# HV_DAC_8ch_DAC_channel.net
KiCad netlist of a schematic drawn in Altium Designer
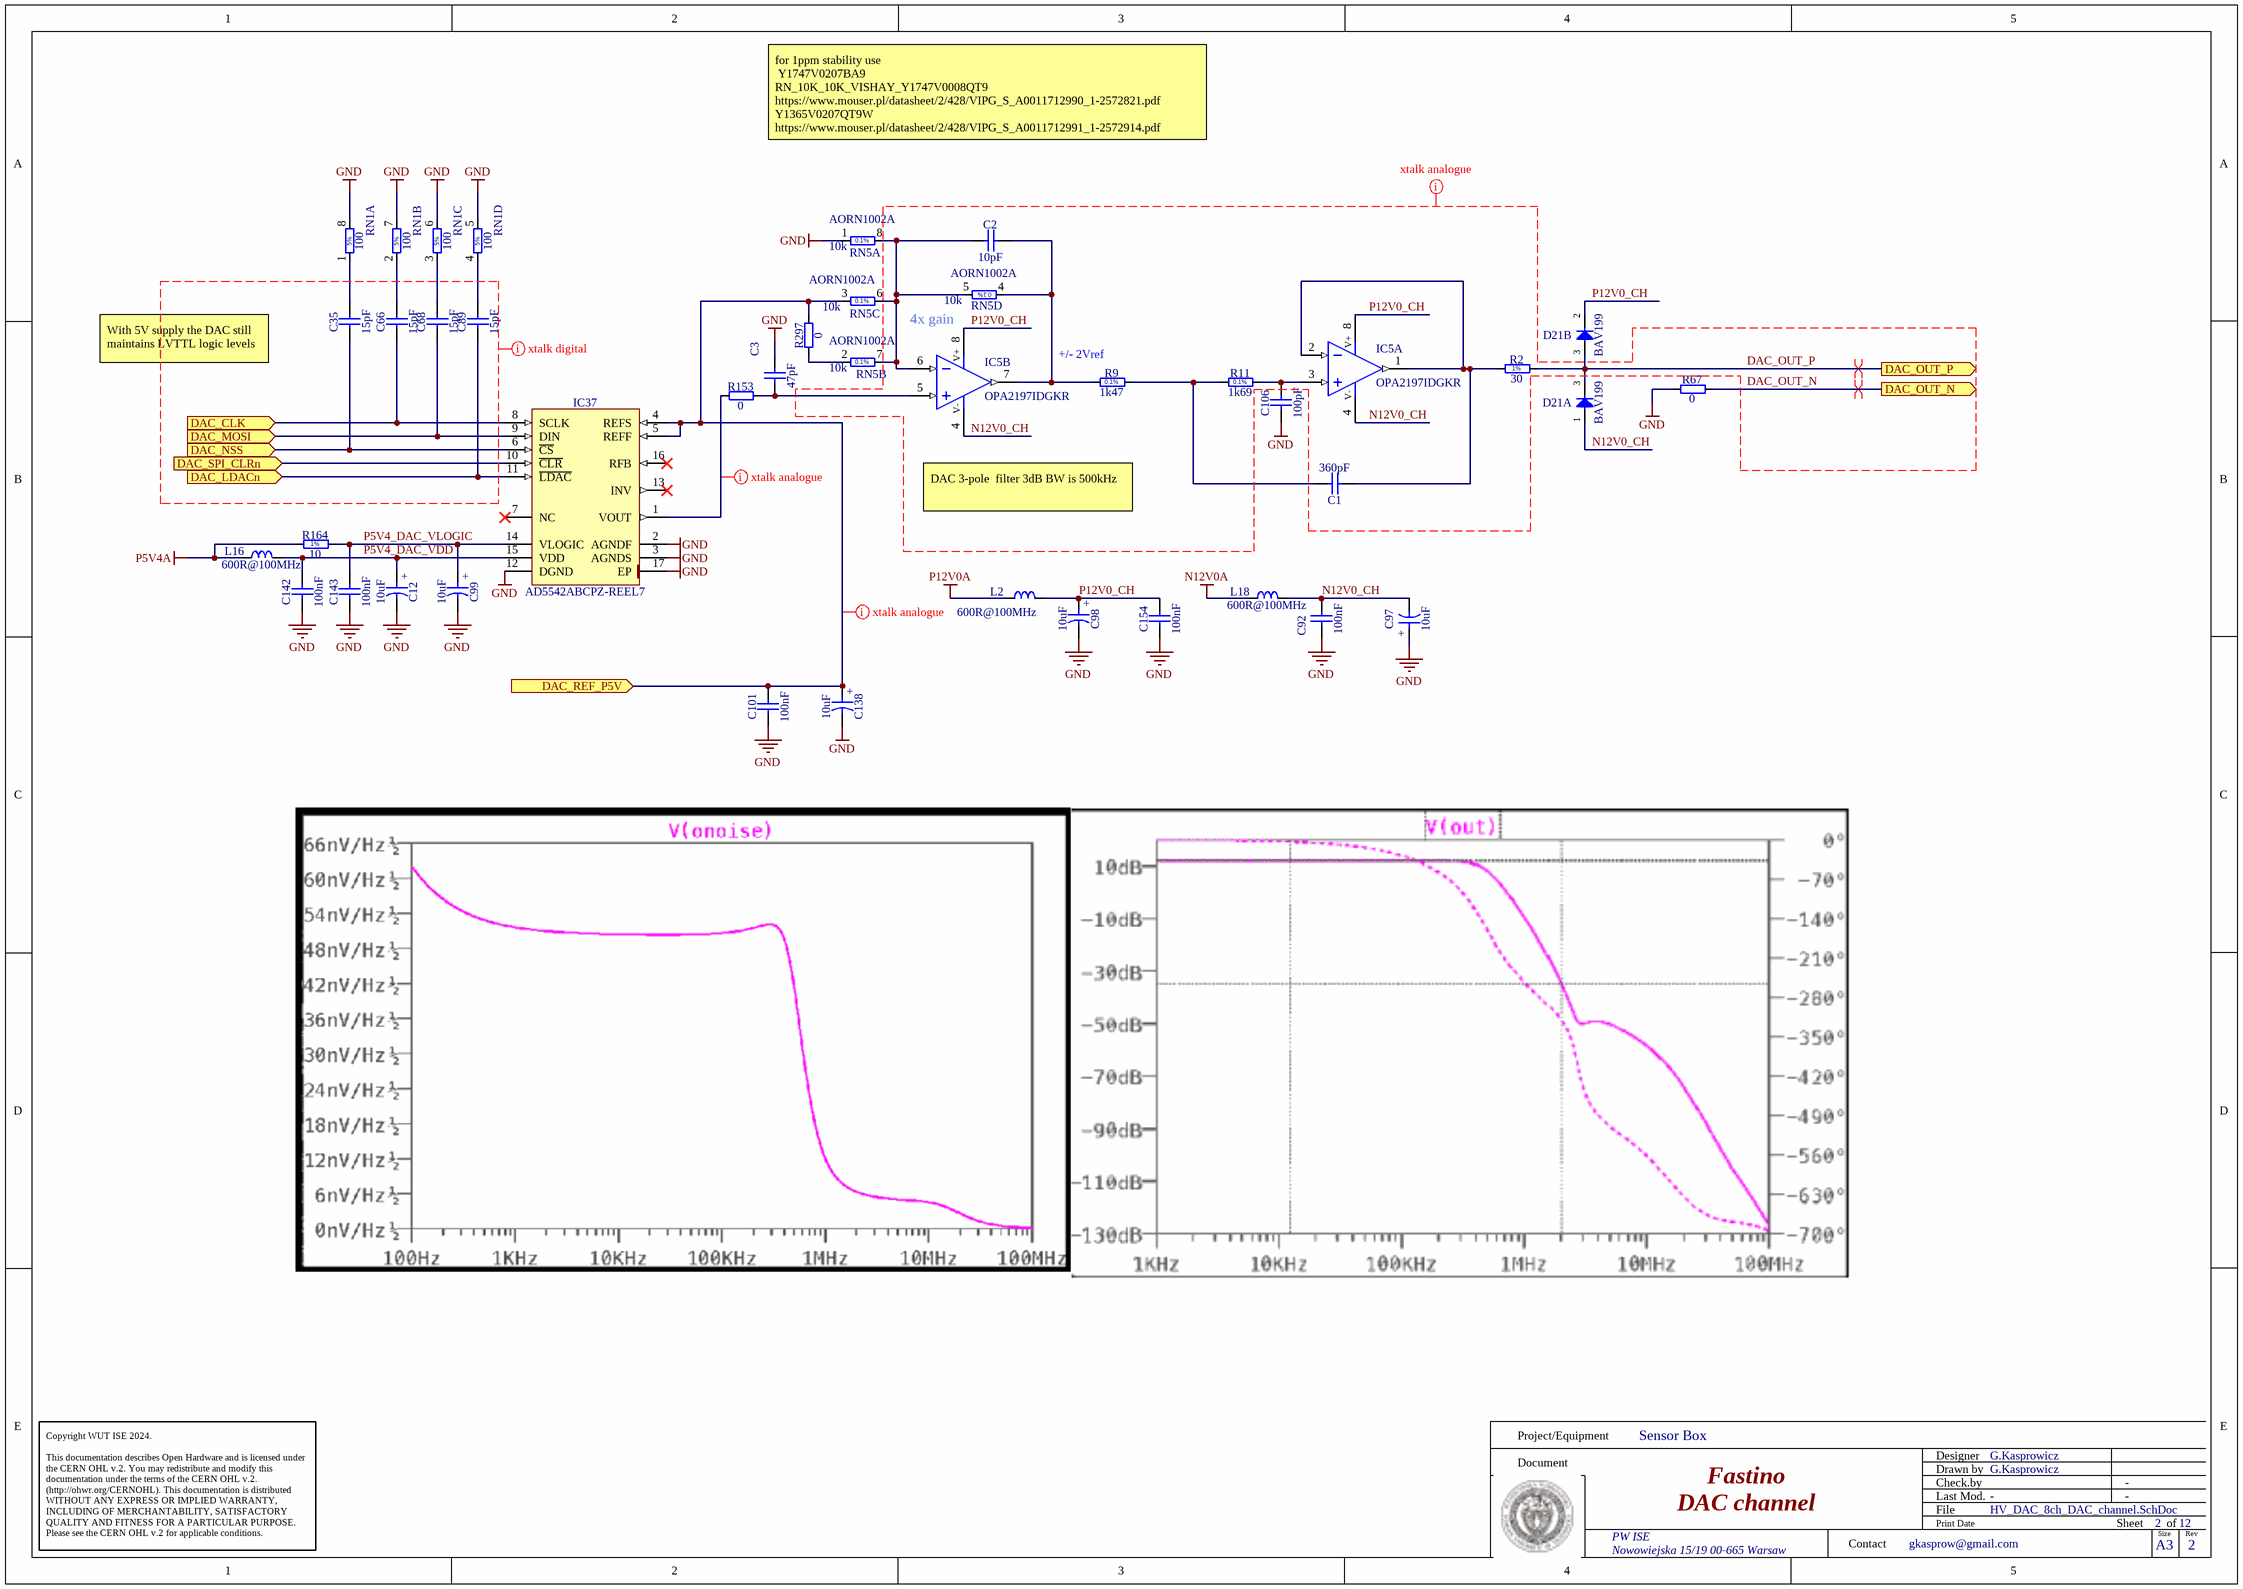
[diagram p0: HV_DAC_8ch_DAC_channel.SchDoc]

(export (version "E")
  (design (tool "Eeschema 10.0.6"))
  (components
    (comp (ref "C1")
      (value "360pF")
      (footprint "CAPC1608X90N")
      (description "SMD Multilayer Chip Ceramic Capacitor")
      (fields
        (field (name "PART NUMBER") "CC0603_360PF_25V_1%_C0G")
        (field (name "VOLTAGE") "25")
        (field (name "AUTHOR") "GK")
      )
      (libsource (lib "Passives_RC") (part "CC0603_360PF_25V_1%_C0G"))
    )
    (comp (ref "C2")
      (value "10pF")
      (footprint "CAPC1005X55N")
      (description "Non-polarised capacitor")
      (fields
        (field (name "PART NUMBER") "CC0402_10PF_50V_5%_C0G")
        (field (name "VOLTAGE") "50V")
        (field (name "AUTHOR") "CERN DEM JLC")
      )
      (libsource (lib "Capacitors") (part "Capacitor - non polarized"))
    )
    (comp (ref "C3")
      (value "47pF")
      (footprint "CAPC1005X55N")
      (description "Non-polarised capacitor")
      (fields
        (field (name "PART NUMBER") "CC0402_47PF_50V_1%_C0G_MURATA_GJM1555C1H470FB01D")
        (field (name "VOLTAGE") "50V")
        (field (name "AUTHOR") "CERN DEM BC")
      )
      (libsource (lib "Capacitors") (part "Capacitor - non polarized"))
    )
    (comp (ref "C12")
      (value "10uF")
      (footprint "CAPMP3216X180N")
      (description "Polarised capacitor")
      (fields
        (field (name "PART NUMBER") "CTE3216-18_10UF_16V_20%_AVX_TCJ")
        (field (name "VOLTAGE") "16V")
        (field (name "AUTHOR") "CERN DEM JLC")
      )
      (libsource (lib "Capacitors") (part "Capacitor - polarized"))
    )
    (comp (ref "C35")
      (value "15pF")
      (footprint "CAPC1608X87N")
      (description "Non-polarised capacitor")
      (fields
        (field (name "PART NUMBER") "CC0603_15PF_50V_5%_NP0")
        (field (name "VOLTAGE") "50V")
        (field (name "AUTHOR") "CERN DEM JLC")
      )
      (libsource (lib "Capacitors") (part "Capacitor - non polarized"))
    )
    (comp (ref "C66")
      (value "15pF")
      (footprint "CAPC1608X87N")
      (description "Non-polarised capacitor")
      (fields
        (field (name "PART NUMBER") "CC0603_15PF_50V_5%_NP0")
        (field (name "VOLTAGE") "50V")
        (field (name "AUTHOR") "CERN DEM JLC")
      )
      (libsource (lib "Capacitors") (part "Capacitor - non polarized"))
    )
    (comp (ref "C68")
      (value "15pF")
      (footprint "CAPC1608X87N")
      (description "Non-polarised capacitor")
      (fields
        (field (name "PART NUMBER") "CC0603_15PF_50V_5%_NP0")
        (field (name "VOLTAGE") "50V")
        (field (name "AUTHOR") "CERN DEM JLC")
      )
      (libsource (lib "Capacitors") (part "Capacitor - non polarized"))
    )
    (comp (ref "C89")
      (value "15pF")
      (footprint "CAPC1608X87N")
      (description "Non-polarised capacitor")
      (fields
        (field (name "PART NUMBER") "CC0603_15PF_50V_5%_NP0")
        (field (name "VOLTAGE") "50V")
        (field (name "AUTHOR") "CERN DEM JLC")
      )
      (libsource (lib "Capacitors") (part "Capacitor - non polarized"))
    )
    (comp (ref "C92")
      (value "100nF")
      (footprint "CAPC1005X55N")
      (description "Non-polarised capacitor")
      (fields
        (field (name "PART NUMBER") "CC0402_100NF_16V_10%_X7R")
        (field (name "VOLTAGE") "16V")
        (field (name "AUTHOR") "CERN DEM JLC")
      )
      (libsource (lib "Capacitors") (part "Capacitor - non polarized"))
    )
    (comp (ref "C97")
      (value "10uF")
      (footprint "CAPMP3216X180N")
      (description "Polarised capacitor")
      (fields
        (field (name "PART NUMBER") "CTE3216-18_10UF_16V_20%_AVX_TCJ")
        (field (name "VOLTAGE") "16V")
        (field (name "AUTHOR") "CERN DEM JLC")
      )
      (libsource (lib "Capacitors") (part "Capacitor - polarized"))
    )
    (comp (ref "C98")
      (value "10uF")
      (footprint "CAPMP3216X180N")
      (description "Polarised capacitor")
      (fields
        (field (name "PART NUMBER") "CTE3216-18_10UF_16V_20%_AVX_TCJ")
        (field (name "VOLTAGE") "16V")
        (field (name "AUTHOR") "CERN DEM JLC")
      )
      (libsource (lib "Capacitors") (part "Capacitor - polarized"))
    )
    (comp (ref "C99")
      (value "10uF")
      (footprint "CAPMP3216X180N")
      (description "Polarised capacitor")
      (fields
        (field (name "PART NUMBER") "CTE3216-18_10UF_16V_20%_AVX_TCJ")
        (field (name "VOLTAGE") "16V")
        (field (name "AUTHOR") "CERN DEM JLC")
      )
      (libsource (lib "Capacitors") (part "Capacitor - polarized"))
    )
    (comp (ref "C101")
      (value "100nF")
      (footprint "CAPC1005X55N")
      (description "Non-polarised capacitor")
      (fields
        (field (name "PART NUMBER") "CC0402_100NF_16V_10%_X7R")
        (field (name "VOLTAGE") "16V")
        (field (name "AUTHOR") "CERN DEM JLC")
      )
      (libsource (lib "Capacitors") (part "Capacitor - non polarized"))
    )
    (comp (ref "C106")
      (value "100pF")
      (footprint "CAPC1608X90N")
      (description "Non-polarised capacitor")
      (fields
        (field (name "PART NUMBER") "CC0603_100PF_50V_1%_NP0")
        (field (name "VOLTAGE") "50V")
        (field (name "AUTHOR") "CERN DEM JLC")
      )
      (libsource (lib "Capacitors") (part "Capacitor - non polarized"))
    )
    (comp (ref "C138")
      (value "10uF")
      (footprint "CAPMP3216X180N")
      (description "Polarised capacitor")
      (fields
        (field (name "PART NUMBER") "CTE3216-18_10UF_16V_20%_AVX_TCJ")
        (field (name "VOLTAGE") "16V")
        (field (name "AUTHOR") "CERN DEM JLC")
      )
      (libsource (lib "Capacitors") (part "Capacitor - polarized"))
    )
    (comp (ref "C142")
      (value "100nF")
      (footprint "CAPC1005X55N")
      (description "Non-polarised capacitor")
      (fields
        (field (name "PART NUMBER") "CC0402_100NF_16V_10%_X7R")
        (field (name "VOLTAGE") "16V")
        (field (name "AUTHOR") "CERN DEM JLC")
      )
      (libsource (lib "Capacitors") (part "Capacitor - non polarized"))
    )
    (comp (ref "C143")
      (value "100nF")
      (footprint "CAPC1005X55N")
      (description "Non-polarised capacitor")
      (fields
        (field (name "PART NUMBER") "CC0402_100NF_16V_10%_X7R")
        (field (name "VOLTAGE") "16V")
        (field (name "AUTHOR") "CERN DEM JLC")
      )
      (libsource (lib "Capacitors") (part "Capacitor - non polarized"))
    )
    (comp (ref "C154")
      (value "100nF")
      (footprint "CAPC1005X55N")
      (description "Non-polarised capacitor")
      (fields
        (field (name "PART NUMBER") "CC0402_100NF_16V_10%_X7R")
        (field (name "VOLTAGE") "16V")
        (field (name "AUTHOR") "CERN DEM JLC")
      )
      (libsource (lib "Capacitors") (part "Capacitor - non polarized"))
    )
    (comp (ref "D21")
      (value "BAV199")
      (footprint "SOT95P240X110-3N")
      (description "Serial Diode")
      (fields
        (field (name "VOLTAGE") "75V")
        (field (name "POWER") "250mW")
        (field (name "AUTHOR") "CERN DEM JMW")
      )
      (libsource (lib "ICs And Semiconductors") (part "Diode x2 A1C3_A3C2"))
    )
    (comp (ref "IC5")
      (value "OPA2197IDGKR")
      (footprint "SOP65P490X110-8N")
      (description "36-V, Precision, Rail-to-Rail Input Output, Low Offset Voltage Op Amp 8-VSSOP")
      (fields (field (name "MANUFACTURER") "TEXAS INSTRUMENTS") (field (name "AUTHOR") "GK"))
      (libsource (lib "ICs_Analog_Interfaces") (part "OA_OPA2197IDGKR"))
    )
    (comp (ref "IC37")
      (value "AD5542ABCPZ-REEL7")
      (footprint "QFN50P300X300X80-17N-S175")
      (description "2.7V to 5.5V, Serial-Input, Voltage-Output, 16-Bit DAC")
      (fields (field (name "MANUFACTURER") "ANALOG DEVICES") (field (name "AUTHOR") "CERN DEM JLC"))
      (libsource (lib "ICs And Semiconductors") (part "AD5542ABCPZ"))
    )
    (comp (ref "L2")
      (value "600R@100MHz")
      (footprint "INDC1005X55N")
      (description "Inductor")
      (fields
        (field (name "PART NUMBER") "IND0402_MURATA_BLM15HD601SN1")
        (field (name "POWER") "300mA")
        (field (name "AUTHOR") "CERN DEM JLC")
      )
      (libsource (lib "Inductors & Transformers") (part "Inductor"))
    )
    (comp (ref "L16")
      (value "600R@100MHz")
      (footprint "INDC1005X55N")
      (description "Inductor")
      (fields
        (field (name "PART NUMBER") "IND0402_MURATA_BLM15HD601SN1")
        (field (name "POWER") "300mA")
        (field (name "AUTHOR") "CERN DEM JLC")
      )
      (libsource (lib "Inductors & Transformers") (part "Inductor"))
    )
    (comp (ref "L18")
      (value "600R@100MHz")
      (footprint "INDC1005X55N")
      (description "Inductor")
      (fields
        (field (name "PART NUMBER") "IND0402_MURATA_BLM15HD601SN1")
        (field (name "POWER") "300mA")
        (field (name "AUTHOR") "CERN DEM JLC")
      )
      (libsource (lib "Inductors & Transformers") (part "Inductor"))
    )
    (comp (ref "R2")
      (value "30")
      (footprint "RESC1608X55N")
      (description "Resistor - 1%")
      (fields
        (field (name "PART NUMBER") "R0603_30R_1%_0.1W_100PPM")
        (field (name "POWER") "0.1W")
        (field (name "AUTHOR") "CERN DEM JLC")
      )
      (libsource (lib "Resistors") (part "Resistor - 1%"))
    )
    (comp (ref "R9")
      (value "1k47")
      (footprint "RESC1608X55N")
      (description "Resistor - 0.1%")
      (fields
        (field (name "PART NUMBER") "R0603_1K47_0.1%_0.063W_10PPM")
        (field (name "POWER") "0.063W")
        (field (name "AUTHOR") "CERN DEM JLC")
      )
      (libsource (lib "Resistors") (part "Resistor - 0.1%"))
    )
    (comp (ref "R11")
      (value "1k69")
      (footprint "RESC1608X55N")
      (description "Resistor - 0.1%")
      (fields
        (field (name "PART NUMBER") "R0603_1K69_0.1%_0.063W_10PPM")
        (field (name "POWER") "0.063W")
        (field (name "AUTHOR") "CERN DEM JLC")
      )
      (libsource (lib "Resistors") (part "Resistor - 0.1%"))
    )
    (comp (ref "R67")
      (value "0")
      (footprint "RESC1608X55N")
      (description "Resistor")
      (fields
        (field (name "PART NUMBER") "R0603_0R_JUMPER")
        (field (name "MANUFACTURER") "GENERIC")
        (field (name "AUTHOR") "CERN DEM JLC")
      )
      (libsource (lib "Resistors") (part "Resistor"))
    )
    (comp (ref "R153")
      (value "0")
      (footprint "RESC1005X40N")
      (description "Resistor")
      (fields
        (field (name "PART NUMBER") "R0402_0R_JUMPER")
        (field (name "MANUFACTURER") "GENERIC")
        (field (name "AUTHOR") "CERN DEM JLC")
      )
      (libsource (lib "Resistors") (part "Resistor"))
    )
    (comp (ref "R164")
      (value "10")
      (footprint "RESC1005X40N")
      (description "Resistor - 1%")
      (fields
        (field (name "PART NUMBER") "R0402_10R_1%_0.0625W_200PPM")
        (field (name "POWER") "0.0625W")
        (field (name "AUTHOR") "CERN DEM JLC")
      )
      (libsource (lib "Resistors") (part "Resistor - 1%"))
    )
    (comp (ref "R297")
      (value "0")
      (footprint "RESC0603X28N")
      (description "Resistor")
      (fields
        (field (name "PART NUMBER") "R0201_0R_JUMPER")
        (field (name "MANUFACTURER") "GENERIC")
        (field (name "AUTHOR") "CERN DEM JLC")
      )
      (libsource (lib "Resistors") (part "Resistor"))
    )
    (comp (ref "RN1")
      (value "100")
      (footprint "RN_YAGEO_TC124")
      (description "DIL8 Resistor Network 4 Isolated Resistor 5%")
      (fields
        (field (name "PART NUMBER") "RN_100R_YAGEO_TC124-JR-07100RL")
        (field (name "POWER") "0.062W")
        (field (name "AUTHOR") "CERN DEM BC")
      )
      (libsource (lib "Passives_RC") (part "RES_RN_100R_YAGEO_TC124-JR-07100RL"))
    )
    (comp (ref "RN5")
      (value "10k")
      (footprint "SOIC127P600X175-8N")
      (description "DIL8 Resistor Network 4 Isolated Resistor 0.1%")
      (fields
        (field (name "PART NUMBER") "RN_10K_VISHAY_AORN1002A")
        (field (name "POWER") "4x0.1W")
        (field (name "MANUFACTURER PART NUMBER") "AORN1002A")
        (field (name "AUTHOR") "CERN DEM JLC")
      )
      (libsource (lib "Resistors") (part "RN DIL8_4xR_Isolated_0.1%"))
    )
  )
  (nets
    (net (code "1") (name "/DAC_CLK") (class "Default")
      (node (ref "C66") (pin "1") (pinfunction "1_1") (pintype "passive"))
      (node (ref "IC37") (pin "8") (pinfunction "SCLK_8") (pintype "input"))
    )
    (net (code "2") (name "/DAC_LDACn") (class "Default")
      (node (ref "C89") (pin "1") (pinfunction "1_1") (pintype "passive"))
      (node (ref "IC37") (pin "11") (pinfunction "~{LDAC}_11") (pintype "input"))
    )
    (net (code "3") (name "/DAC_MOSI") (class "Default")
      (node (ref "C68") (pin "1") (pinfunction "1_1") (pintype "passive"))
      (node (ref "IC37") (pin "9") (pinfunction "DIN_9") (pintype "input"))
    )
    (net (code "4") (name "/DAC_NSS") (class "Default")
      (node (ref "C35") (pin "1") (pinfunction "1_1") (pintype "passive"))
      (node (ref "IC37") (pin "6") (pinfunction "~{CS}_6") (pintype "input"))
    )
    (net (code "5") (name "/DAC_OUT_N") (class "Default")
      (node (ref "R67") (pin "2") (pinfunction "2_2") (pintype "passive"))
    )
    (net (code "6") (name "/DAC_OUT_P") (class "Default")
      (node (ref "D21") (pin "3") (pinfunction "COMAC_3") (pintype "passive"))
      (node (ref "R2") (pin "2") (pinfunction "2_2") (pintype "passive"))
    )
    (net (code "7") (name "/DAC_REF_P5V") (class "Default")
      (node (ref "C101") (pin "2") (pinfunction "2_2") (pintype "passive"))
      (node (ref "C138") (pin "1") (pinfunction "1_1") (pintype "passive"))
      (node (ref "IC37") (pin "4") (pinfunction "REFS_4") (pintype "input"))
      (node (ref "IC37") (pin "5") (pinfunction "REFF_5") (pintype "input"))
      (node (ref "R297") (pin "2") (pinfunction "2_2") (pintype "passive"))
      (node (ref "RN5") (pin "3") (pinfunction "3_3") (pintype "passive"))
    )
    (net (code "8") (name "/DAC_SPI_CLRn") (class "Default")
      (node (ref "IC37") (pin "10") (pinfunction "~{CLR}_10") (pintype "input"))
    )
    (net (code "9") (name "/N12V0_CH") (class "Default")
      (node (ref "C92") (pin "2") (pinfunction "2_2") (pintype "passive"))
      (node (ref "C97") (pin "2") (pinfunction "2_2") (pintype "passive"))
      (node (ref "D21") (pin "1") (pinfunction "A_1") (pintype "passive"))
      (node (ref "IC5") (pin "4") (pinfunction "V-_4") (pintype "power_in"))
      (node (ref "L18") (pin "2") (pinfunction "2_2") (pintype "passive"))
    )
    (net (code "10") (name "/P5V4_DAC_VDD") (class "Default")
      (node (ref "C12") (pin "1") (pinfunction "1_1") (pintype "passive"))
      (node (ref "C142") (pin "2") (pinfunction "2_2") (pintype "passive"))
      (node (ref "IC37") (pin "15") (pinfunction "VDD_15") (pintype "power_in"))
      (node (ref "L16") (pin "2") (pinfunction "2_2") (pintype "passive"))
    )
    (net (code "11") (name "/P5V4_DAC_VLOGIC") (class "Default")
      (node (ref "C143") (pin "2") (pinfunction "2_2") (pintype "passive"))
      (node (ref "C99") (pin "1") (pinfunction "1_1") (pintype "passive"))
      (node (ref "IC37") (pin "14") (pinfunction "VLOGIC_14") (pintype "power_in"))
      (node (ref "R164") (pin "2") (pinfunction "2_2") (pintype "passive"))
    )
    (net (code "12") (name "/P12V0_CH") (class "Default")
      (node (ref "C154") (pin "2") (pinfunction "2_2") (pintype "passive"))
      (node (ref "C98") (pin "1") (pinfunction "1_1") (pintype "passive"))
      (node (ref "D21") (pin "2") (pinfunction "C_2") (pintype "passive"))
      (node (ref "IC5") (pin "8") (pinfunction "V+_8") (pintype "power_in"))
      (node (ref "L2") (pin "2") (pinfunction "2_2") (pintype "passive"))
    )
    (net (code "13") (name "GND") (class "Default")
      (node (ref "C101") (pin "1") (pinfunction "1_1") (pintype "passive"))
      (node (ref "C106") (pin "1") (pinfunction "1_1") (pintype "passive"))
      (node (ref "C12") (pin "2") (pinfunction "2_2") (pintype "passive"))
      (node (ref "C138") (pin "2") (pinfunction "2_2") (pintype "passive"))
      (node (ref "C142") (pin "1") (pinfunction "1_1") (pintype "passive"))
      (node (ref "C143") (pin "1") (pinfunction "1_1") (pintype "passive"))
      (node (ref "C154") (pin "1") (pinfunction "1_1") (pintype "passive"))
      (node (ref "C3") (pin "2") (pinfunction "2_2") (pintype "passive"))
      (node (ref "C92") (pin "1") (pinfunction "1_1") (pintype "passive"))
      (node (ref "C97") (pin "1") (pinfunction "1_1") (pintype "passive"))
      (node (ref "C98") (pin "2") (pinfunction "2_2") (pintype "passive"))
      (node (ref "C99") (pin "2") (pinfunction "2_2") (pintype "passive"))
      (node (ref "IC37") (pin "12") (pinfunction "DGND_12") (pintype "power_in"))
      (node (ref "IC37") (pin "17") (pinfunction "EP_17") (pintype "power_in"))
      (node (ref "IC37") (pin "2") (pinfunction "AGNDF_2") (pintype "power_in"))
      (node (ref "IC37") (pin "3") (pinfunction "AGNDS_3") (pintype "power_in"))
      (node (ref "R67") (pin "1") (pinfunction "1_1") (pintype "passive"))
      (node (ref "RN1") (pin "5") (pinfunction "5_5") (pintype "passive"))
      (node (ref "RN1") (pin "6") (pinfunction "6_6") (pintype "passive"))
      (node (ref "RN1") (pin "7") (pinfunction "7_7") (pintype "passive"))
      (node (ref "RN1") (pin "8") (pinfunction "8_8") (pintype "passive"))
      (node (ref "RN5") (pin "1") (pinfunction "1_1") (pintype "passive"))
    )
    (net (code "14") (name "N12V0A") (class "Default")
      (node (ref "L18") (pin "1") (pinfunction "1_1") (pintype "passive"))
    )
    (net (code "15") (name "Net-(C1-Pad2)") (class "Default")
      (node (ref "C1") (pin "2") (pinfunction "2_2") (pintype "passive"))
      (node (ref "R11") (pin "1") (pinfunction "1_1") (pintype "passive"))
      (node (ref "R9") (pin "2") (pinfunction "2_2") (pintype "passive"))
    )
    (net (code "16") (name "Net-(C35-Pad2)") (class "Default")
      (node (ref "C35") (pin "2") (pinfunction "2_2") (pintype "passive"))
      (node (ref "RN1") (pin "1") (pinfunction "1_1") (pintype "passive"))
    )
    (net (code "17") (name "Net-(C66-Pad2)") (class "Default")
      (node (ref "C66") (pin "2") (pinfunction "2_2") (pintype "passive"))
      (node (ref "RN1") (pin "2") (pinfunction "2_2") (pintype "passive"))
    )
    (net (code "18") (name "Net-(C68-Pad2)") (class "Default")
      (node (ref "C68") (pin "2") (pinfunction "2_2") (pintype "passive"))
      (node (ref "RN1") (pin "3") (pinfunction "3_3") (pintype "passive"))
    )
    (net (code "19") (name "Net-(C89-Pad2)") (class "Default")
      (node (ref "C89") (pin "2") (pinfunction "2_2") (pintype "passive"))
      (node (ref "RN1") (pin "4") (pinfunction "4_4") (pintype "passive"))
    )
    (net (code "20") (name "Net-(IC5A-IN+)") (class "Default")
      (node (ref "C106") (pin "2") (pinfunction "2_2") (pintype "passive"))
      (node (ref "IC5") (pin "3") (pinfunction "IN+_3") (pintype "input"))
      (node (ref "R11") (pin "2") (pinfunction "2_2") (pintype "passive"))
    )
    (net (code "21") (name "Net-(IC5A-IN-)") (class "Default")
      (node (ref "C1") (pin "1") (pinfunction "1_1") (pintype "passive"))
      (node (ref "IC5") (pin "1") (pinfunction "OUT_1") (pintype "output"))
      (node (ref "IC5") (pin "2") (pinfunction "IN-_2") (pintype "input"))
      (node (ref "R2") (pin "1") (pinfunction "1_1") (pintype "passive"))
    )
    (net (code "22") (name "Net-(IC5B-IN+)") (class "Default")
      (node (ref "C3") (pin "1") (pinfunction "1_1") (pintype "passive"))
      (node (ref "IC5") (pin "5") (pinfunction "IN+_5") (pintype "input"))
      (node (ref "R153") (pin "2") (pinfunction "2_2") (pintype "passive"))
    )
    (net (code "23") (name "Net-(IC5B-IN-)") (class "Default")
      (node (ref "C2") (pin "1") (pinfunction "1_1") (pintype "passive"))
      (node (ref "IC5") (pin "6") (pinfunction "IN-_6") (pintype "input"))
      (node (ref "RN5") (pin "5") (pinfunction "5_5") (pintype "passive"))
      (node (ref "RN5") (pin "6") (pinfunction "6_6") (pintype "passive"))
      (node (ref "RN5") (pin "7") (pinfunction "7_7") (pintype "passive"))
      (node (ref "RN5") (pin "8") (pinfunction "8_8") (pintype "passive"))
    )
    (net (code "24") (name "Net-(IC5B-OUT)") (class "Default")
      (node (ref "C2") (pin "2") (pinfunction "2_2") (pintype "passive"))
      (node (ref "IC5") (pin "7") (pinfunction "OUT_7") (pintype "output"))
      (node (ref "R9") (pin "1") (pinfunction "1_1") (pintype "passive"))
      (node (ref "RN5") (pin "4") (pinfunction "4_4") (pintype "passive"))
    )
    (net (code "25") (name "Net-(IC37-VOUT)") (class "Default")
      (node (ref "IC37") (pin "1") (pinfunction "VOUT_1") (pintype "output"))
      (node (ref "R153") (pin "1") (pinfunction "1_1") (pintype "passive"))
    )
    (net (code "26") (name "Net-(R297-Pad1)") (class "Default")
      (node (ref "R297") (pin "1") (pinfunction "1_1") (pintype "passive"))
      (node (ref "RN5") (pin "2") (pinfunction "2_2") (pintype "passive"))
    )
    (net (code "27") (name "P5V4A") (class "Default")
      (node (ref "L16") (pin "1") (pinfunction "1_1") (pintype "passive"))
      (node (ref "R164") (pin "1") (pinfunction "1_1") (pintype "passive"))
    )
    (net (code "28") (name "P12V0A") (class "Default")
      (node (ref "L2") (pin "1") (pinfunction "1_1") (pintype "passive"))
    )
    (net (code "29") (name "unconnected-(IC37-INV-Pad13)") (class "Default")
      (node (ref "IC37") (pin "13") (pinfunction "INV_13") (pintype "output+no_connect"))
    )
    (net (code "30") (name "unconnected-(IC37-NC-Pad7)") (class "Default")
      (node (ref "IC37") (pin "7") (pinfunction "NC_7") (pintype "passive+no_connect"))
    )
    (net (code "31") (name "unconnected-(IC37-RFB-Pad16)") (class "Default")
      (node (ref "IC37") (pin "16") (pinfunction "RFB_16") (pintype "input+no_connect"))
    )
  )
)
